# spectrum_2kHz_250Hz.net
KiCad netlist of a schematic drawn in Altium Designer
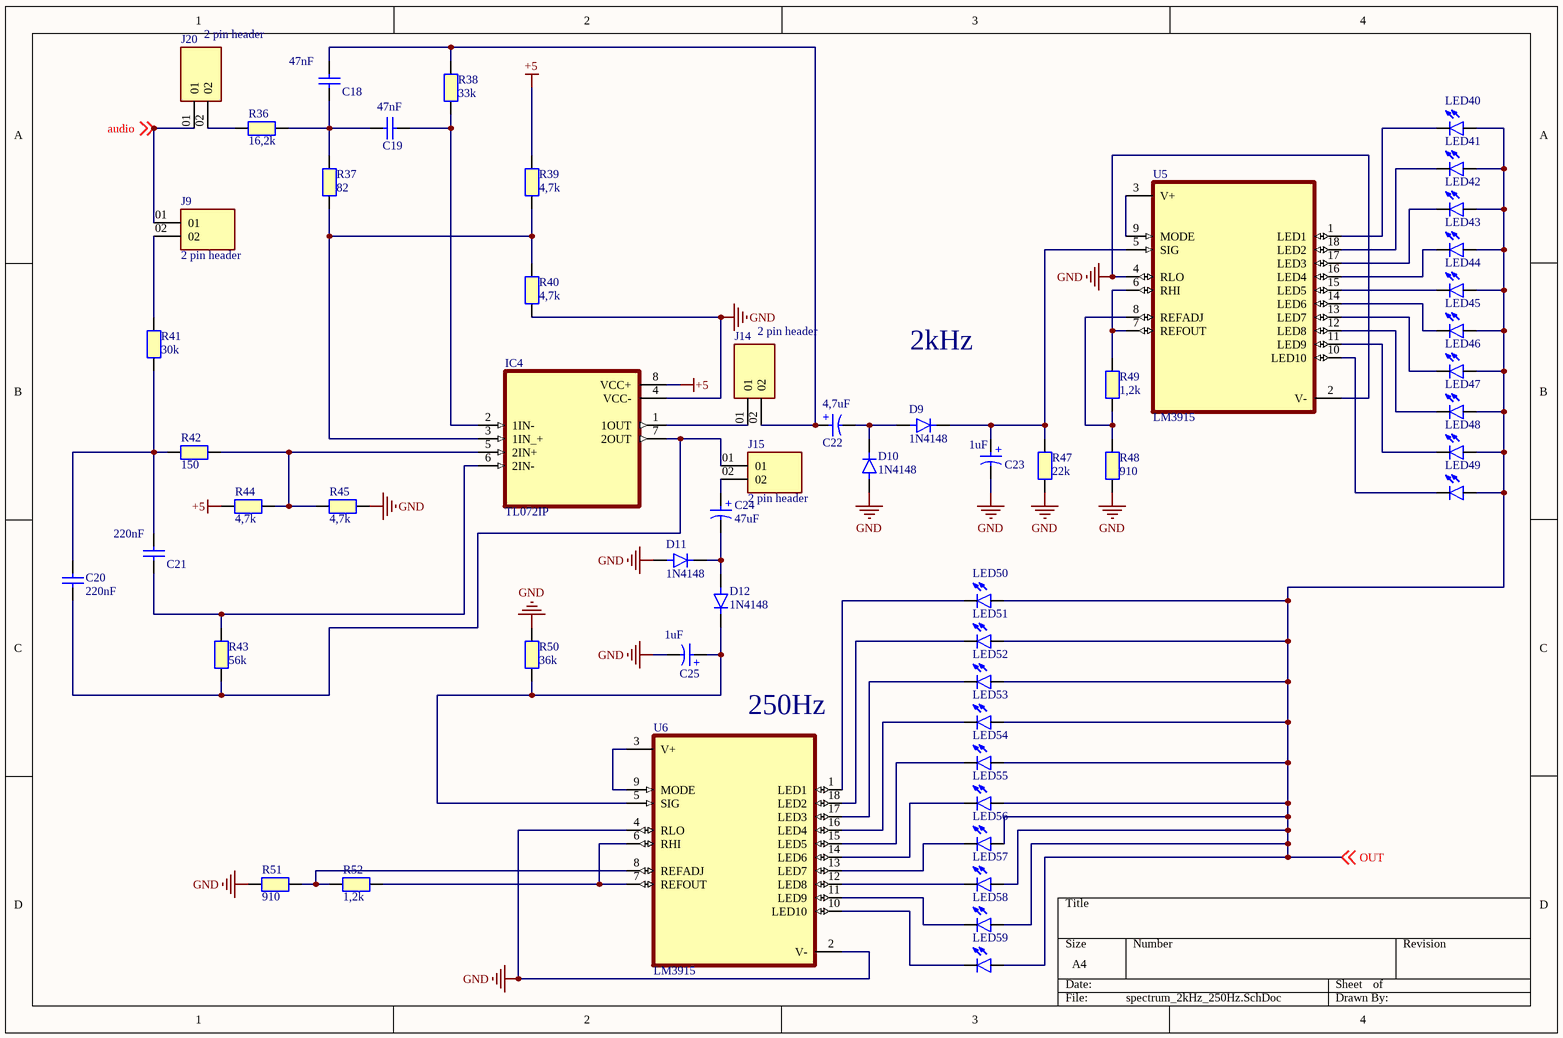
[diagram p0: spectrum_2kHz_250Hz.SchDoc]

(export (version "E")
  (design (tool "Eeschema 10.0.6"))
  (components
    (comp (ref "C18")
      (value "47nF")
      (footprint "CAPC2012X65N")
      (description "47nF ceramic")
      (fields
        (field (name "MANUFACTURER PART NUMBER") "885012004008")
        (field (name "MANUFACTURER") "Wurth Elektronik")
      )
      (libsource (lib "SpectrumComponents") (part "885012004008"))
    )
    (comp (ref "C19")
      (value "47nF")
      (footprint "CAPC2012X65N")
      (description "47nF ceramic")
      (fields
        (field (name "MANUFACTURER PART NUMBER") "885012004008")
        (field (name "MANUFACTURER") "Wurth Elektronik")
      )
      (libsource (lib "SpectrumComponents") (part "885012004008"))
    )
    (comp (ref "C20")
      (value "220nF")
      (footprint "CAPC2012X65N")
      (description "220nF ceramic")
      (fields
        (field (name "MANUFACTURER PART NUMBER") "885012004008")
        (field (name "MANUFACTURER") "Wurth Elektronik")
      )
      (libsource (lib "SpectrumComponents") (part "885012004008"))
    )
    (comp (ref "C21")
      (value "220nF")
      (footprint "CAPC2012X65N")
      (description "220nF ceramic")
      (fields
        (field (name "MANUFACTURER PART NUMBER") "885012004008")
        (field (name "MANUFACTURER") "Wurth Elektronik")
      )
      (libsource (lib "SpectrumComponents") (part "885012004008"))
    )
    (comp (ref "C22")
      (value "4,7uF")
      (footprint "WCAP-ATG8_D5H11")
      (description "Elco 4,7uF")
      (fields
        (field (name "MANUFACTURER PART NUMBER") "860010272005")
        (field (name "MANUFACTURER") "Wurth Elektronik")
      )
      (libsource (lib "SpectrumComponents") (part "860010272005"))
    )
    (comp (ref "C23")
      (value "1uF")
      (footprint "WCAP-ATG8_D5H11")
      (description "WCAP-ATG8 Aluminum Electrolytic Capacitor, Radial, THT, D5 x H11mm, 1uF, 10V")
      (fields
        (field (name "MANUFACTURER PART NUMBER") "860010272005")
        (field (name "MANUFACTURER") "Wurth Elektronik")
      )
      (libsource (lib "SpectrumComponents") (part "860010272005"))
    )
    (comp (ref "C24")
      (value "47uF")
      (footprint "WCAP-ATG8_D5H11")
      (description "Elco 47uF")
      (fields
        (field (name "MANUFACTURER PART NUMBER") "860010272005")
        (field (name "MANUFACTURER") "Wurth Elektronik")
      )
      (libsource (lib "SpectrumComponents") (part "860010272005"))
    )
    (comp (ref "C25")
      (value "1uF")
      (footprint "WCAP-ATG8_D5H11")
      (description "WCAP-ATG8 Aluminum Electrolytic Capacitor, Radial, THT, D5 x H11mm, 1µF, 10V")
      (fields
        (field (name "MANUFACTURER PART NUMBER") "860010272005")
        (field (name "MANUFACTURER") "Wurth Elektronik")
      )
      (libsource (lib "SpectrumComponents") (part "860010272005"))
    )
    (comp (ref "D9")
      (value "1N4148")
      (footprint "DIOAD829W49L456D191")
      (description "Diode Standard 75V 200mA Surface Mount SOD-523F")
      (fields (field (name "MF") "ON Semiconductor"))
      (libsource (lib "SpectrumComponents") (part "1N4148"))
    )
    (comp (ref "D10")
      (value "1N4148")
      (footprint "DIOAD829W49L456D191")
      (description "Diode Standard 75V 200mA Surface Mount SOD-523F")
      (fields (field (name "MF") "ON Semiconductor"))
      (libsource (lib "SpectrumComponents") (part "1N4148"))
    )
    (comp (ref "D11")
      (value "1N4148")
      (footprint "DIOAD829W49L456D191")
      (description "Diode Standard 75V 200mA Surface Mount SOD-523F")
      (fields (field (name "MF") "ON Semiconductor"))
      (libsource (lib "SpectrumComponents") (part "1N4148"))
    )
    (comp (ref "D12")
      (value "1N4148")
      (footprint "DIOAD829W49L456D191")
      (description "Diode Standard 75V 200mA Surface Mount SOD-523F")
      (fields (field (name "MF") "ON Semiconductor"))
      (libsource (lib "SpectrumComponents") (part "1N4148"))
    )
    (comp (ref "IC4")
      (value "TL072IP")
      (footprint "DIP794W45P254L959H508Q8")
      (description "Dual, 30-V, 3-MHz, high slew rate (13-V/Âµs), In to V+, JFET-input op amp")
      (fields (field (name "MF") "Texas Instruments"))
      (libsource (lib "SpectrumComponents") (part "TL072IP"))
    )
    (comp (ref "J9")
      (value "2 pin header")
      (footprint "SpectrumComponents:SAMTEC_HTSW-102-07-TM-S")
      (description "2 pin header Jumper")
      (fields (field (name "MP") "HTSW10207TMS") (field (name "MF") "Samtec"))
      (libsource (lib "") (part "2 pin header_1"))
    )
    (comp (ref "J14")
      (value "2 pin header")
      (footprint "SpectrumComponents:SAMTEC_HTSW-102-07-TM-S")
      (description "2 pin header Jumper")
      (fields (field (name "MP") "HTSW10207TMS") (field (name "MF") "Samtec"))
      (libsource (lib "SpectrumComponents") (part "2 pin header"))
    )
    (comp (ref "J15")
      (value "2 pin header")
      (footprint "SpectrumComponents:SAMTEC_HTSW-102-07-TM-S")
      (description "2 pin header Jumper")
      (fields (field (name "MP") "HTSW10207TMS") (field (name "MF") "Samtec"))
      (libsource (lib "") (part "2 pin header_1"))
    )
    (comp (ref "J20")
      (value "2 pin header")
      (footprint "SpectrumComponents:SAMTEC_HTSW-102-07-TM-S")
      (description "2 pin header Jumper")
      (fields (field (name "MP") "HTSW10207TMS") (field (name "MF") "Samtec"))
      (libsource (lib "SpectrumComponents") (part "2 pin header"))
    )
    (comp (ref "LED40")
      (value "LED 2x3x4")
      (footprint "LED 2x3x4mm")
      (description "Green 569nm LED Indication - Discrete 1.9V Radial")
      (fields (field (name "MP") "TLLG4400") (field (name "MF") "Vishay Semiconductors"))
      (libsource (lib "SpectrumComponents") (part "LED 2x3x4"))
    )
    (comp (ref "LED41")
      (value "LED 2x3x4")
      (footprint "LED 2x3x4mm")
      (description "Green 569nm LED Indication - Discrete 1.9V Radial")
      (fields (field (name "MP") "TLLG4400") (field (name "MF") "Vishay Semiconductors"))
      (libsource (lib "SpectrumComponents") (part "LED 2x3x4"))
    )
    (comp (ref "LED42")
      (value "LED 2x3x4")
      (footprint "LED 2x3x4mm")
      (description "Green 569nm LED Indication - Discrete 1.9V Radial")
      (fields (field (name "MP") "TLLG4400") (field (name "MF") "Vishay Semiconductors"))
      (libsource (lib "SpectrumComponents") (part "LED 2x3x4"))
    )
    (comp (ref "LED43")
      (value "LED 2x3x4")
      (footprint "LED 2x3x4mm")
      (description "Green 569nm LED Indication - Discrete 1.9V Radial")
      (fields (field (name "MP") "TLLG4400") (field (name "MF") "Vishay Semiconductors"))
      (libsource (lib "SpectrumComponents") (part "LED 2x3x4"))
    )
    (comp (ref "LED44")
      (value "LED 2x3x4")
      (footprint "LED 2x3x4mm")
      (description "Green 569nm LED Indication - Discrete 1.9V Radial")
      (fields (field (name "MP") "TLLG4400") (field (name "MF") "Vishay Semiconductors"))
      (libsource (lib "SpectrumComponents") (part "LED 2x3x4"))
    )
    (comp (ref "LED45")
      (value "LED 2x3x4")
      (footprint "LED 2x3x4mm")
      (description "Green 569nm LED Indication - Discrete 1.9V Radial")
      (fields (field (name "MP") "TLLG4400") (field (name "MF") "Vishay Semiconductors"))
      (libsource (lib "SpectrumComponents") (part "LED 2x3x4"))
    )
    (comp (ref "LED46")
      (value "LED 2x3x4")
      (footprint "LED 2x3x4mm")
      (description "Green 569nm LED Indication - Discrete 1.9V Radial")
      (fields (field (name "MP") "TLLG4400") (field (name "MF") "Vishay Semiconductors"))
      (libsource (lib "SpectrumComponents") (part "LED 2x3x4"))
    )
    (comp (ref "LED47")
      (value "LED 2x3x4")
      (footprint "LED 2x3x4mm")
      (description "Green 569nm LED Indication - Discrete 1.9V Radial")
      (fields (field (name "MP") "TLLG4400") (field (name "MF") "Vishay Semiconductors"))
      (libsource (lib "SpectrumComponents") (part "LED 2x3x4"))
    )
    (comp (ref "LED48")
      (value "LED 2x3x4")
      (footprint "LED 2x3x4mm")
      (description "Green 569nm LED Indication - Discrete 1.9V Radial")
      (fields (field (name "MP") "TLLG4400") (field (name "MF") "Vishay Semiconductors"))
      (libsource (lib "SpectrumComponents") (part "LED 2x3x4"))
    )
    (comp (ref "LED49")
      (value "LED 2x3x4")
      (footprint "LED 2x3x4mm")
      (description "Green 569nm LED Indication - Discrete 1.9V Radial")
      (fields (field (name "MP") "TLLG4400") (field (name "MF") "Vishay Semiconductors"))
      (libsource (lib "SpectrumComponents") (part "LED 2x3x4"))
    )
    (comp (ref "LED50")
      (value "LED 2x3x4")
      (footprint "LED 2x3x4mm")
      (description "Green 569nm LED Indication - Discrete 1.9V Radial")
      (fields (field (name "MP") "TLLG4400") (field (name "MF") "Vishay Semiconductors"))
      (libsource (lib "SpectrumComponents") (part "LED 2x3x4"))
    )
    (comp (ref "LED51")
      (value "LED 2x3x4")
      (footprint "LED 2x3x4mm")
      (description "Green 569nm LED Indication - Discrete 1.9V Radial")
      (fields (field (name "MP") "TLLG4400") (field (name "MF") "Vishay Semiconductors"))
      (libsource (lib "SpectrumComponents") (part "LED 2x3x4"))
    )
    (comp (ref "LED52")
      (value "LED 2x3x4")
      (footprint "LED 2x3x4mm")
      (description "Green 569nm LED Indication - Discrete 1.9V Radial")
      (fields (field (name "MP") "TLLG4400") (field (name "MF") "Vishay Semiconductors"))
      (libsource (lib "SpectrumComponents") (part "LED 2x3x4"))
    )
    (comp (ref "LED53")
      (value "LED 2x3x4")
      (footprint "LED 2x3x4mm")
      (description "Green 569nm LED Indication - Discrete 1.9V Radial")
      (fields (field (name "MP") "TLLG4400") (field (name "MF") "Vishay Semiconductors"))
      (libsource (lib "SpectrumComponents") (part "LED 2x3x4"))
    )
    (comp (ref "LED54")
      (value "LED 2x3x4")
      (footprint "LED 2x3x4mm")
      (description "Green 569nm LED Indication - Discrete 1.9V Radial")
      (fields (field (name "MP") "TLLG4400") (field (name "MF") "Vishay Semiconductors"))
      (libsource (lib "SpectrumComponents") (part "LED 2x3x4"))
    )
    (comp (ref "LED55")
      (value "LED 2x3x4")
      (footprint "LED 2x3x4mm")
      (description "Green 569nm LED Indication - Discrete 1.9V Radial")
      (fields (field (name "MP") "TLLG4400") (field (name "MF") "Vishay Semiconductors"))
      (libsource (lib "SpectrumComponents") (part "LED 2x3x4"))
    )
    (comp (ref "LED56")
      (value "LED 2x3x4")
      (footprint "LED 2x3x4mm")
      (description "Green 569nm LED Indication - Discrete 1.9V Radial")
      (fields (field (name "MP") "TLLG4400") (field (name "MF") "Vishay Semiconductors"))
      (libsource (lib "SpectrumComponents") (part "LED 2x3x4"))
    )
    (comp (ref "LED57")
      (value "LED 2x3x4")
      (footprint "LED 2x3x4mm")
      (description "Green 569nm LED Indication - Discrete 1.9V Radial")
      (fields (field (name "MP") "TLLG4400") (field (name "MF") "Vishay Semiconductors"))
      (libsource (lib "SpectrumComponents") (part "LED 2x3x4"))
    )
    (comp (ref "LED58")
      (value "LED 2x3x4")
      (footprint "LED 2x3x4mm")
      (description "Green 569nm LED Indication - Discrete 1.9V Radial")
      (fields (field (name "MP") "TLLG4400") (field (name "MF") "Vishay Semiconductors"))
      (libsource (lib "SpectrumComponents") (part "LED 2x3x4"))
    )
    (comp (ref "LED59")
      (value "LED 2x3x4")
      (footprint "LED 2x3x4mm")
      (description "Green 569nm LED Indication - Discrete 1.9V Radial")
      (fields (field (name "MP") "TLLG4400") (field (name "MF") "Vishay Semiconductors"))
      (libsource (lib "SpectrumComponents") (part "LED 2x3x4"))
    )
    (comp (ref "R36")
      (value "16,2k")
      (footprint "RESC2012X50N")
      (description "16.2k Resistor 0805")
      (fields (field (name "PART NUMBER") "TNPW080510K0BETA") (field (name "MANUFACTURER") "Vishay Dale"))
      (libsource (lib "") (part "RESISTOR 0805_3"))
    )
    (comp (ref "R37")
      (value "82")
      (footprint "RESC2012X50N")
      (description "82Ohm Resistor 0805")
      (fields (field (name "PART NUMBER") "TNPW080510K0BETA") (field (name "MANUFACTURER") "Vishay Dale"))
      (libsource (lib "SpectrumComponents") (part "RESISTOR 0805"))
    )
    (comp (ref "R38")
      (value "33k")
      (footprint "RESC2012X50N")
      (description "33k Resistor 0805")
      (fields (field (name "PART NUMBER") "TNPW080510K0BETA") (field (name "MANUFACTURER") "Vishay Dale"))
      (libsource (lib "SpectrumComponents") (part "RESISTOR 0805"))
    )
    (comp (ref "R39")
      (value "4,7k")
      (footprint "RESC2012X50N")
      (description "4,7k Resistor 0805")
      (fields (field (name "PART NUMBER") "TNPW080510K0BETA") (field (name "MANUFACTURER") "Vishay Dale"))
      (libsource (lib "SpectrumComponents") (part "RESISTOR 0805"))
    )
    (comp (ref "R40")
      (value "4,7k")
      (footprint "RESC2012X50N")
      (description "4,7k Resistor 0805")
      (fields (field (name "PART NUMBER") "TNPW080510K0BETA") (field (name "MANUFACTURER") "Vishay Dale"))
      (libsource (lib "SpectrumComponents") (part "RESISTOR 0805"))
    )
    (comp (ref "R41")
      (value "30k")
      (footprint "RESC2012X50N")
      (description "30k Resistor 0805")
      (fields (field (name "PART NUMBER") "TNPW080510K0BETA") (field (name "MANUFACTURER") "Vishay Dale"))
      (libsource (lib "SpectrumComponents") (part "RESISTOR 0805"))
    )
    (comp (ref "R42")
      (value "150")
      (footprint "RESC2012X50N")
      (description "150 Resistor 0805")
      (fields (field (name "PART NUMBER") "TNPW080510K0BETA") (field (name "MANUFACTURER") "Vishay Dale"))
      (libsource (lib "") (part "RESISTOR 0805_1"))
    )
    (comp (ref "R43")
      (value "56k")
      (footprint "RESC2012X50N")
      (description "56k Resistor 0805")
      (fields (field (name "PART NUMBER") "TNPW080510K0BETA") (field (name "MANUFACTURER") "Vishay Dale"))
      (libsource (lib "SpectrumComponents") (part "RESISTOR 0805"))
    )
    (comp (ref "R44")
      (value "4,7k")
      (footprint "RESC2012X50N")
      (description "4,7k Resistor 0805")
      (fields (field (name "PART NUMBER") "TNPW080510K0BETA") (field (name "MANUFACTURER") "Vishay Dale"))
      (libsource (lib "") (part "RESISTOR 0805_1"))
    )
    (comp (ref "R45")
      (value "4,7k")
      (footprint "RESC2012X50N")
      (description "4,7k Resistor 0805")
      (fields (field (name "PART NUMBER") "TNPW080510K0BETA") (field (name "MANUFACTURER") "Vishay Dale"))
      (libsource (lib "") (part "RESISTOR 0805_3"))
    )
    (comp (ref "R47")
      (value "22k")
      (footprint "RESC2012X50N")
      (description "22k Resistor 0805")
      (fields (field (name "PART NUMBER") "TNPW080510K0BETA") (field (name "MANUFACTURER") "Vishay Dale"))
      (libsource (lib "SpectrumComponents") (part "RESISTOR 0805"))
    )
    (comp (ref "R48")
      (value "910")
      (footprint "RESC2012X50N")
      (description "910 Resistor 0805")
      (fields (field (name "PART NUMBER") "TNPW080510K0BETA") (field (name "MANUFACTURER") "Vishay Dale"))
      (libsource (lib "") (part "RESISTOR 0805_2"))
    )
    (comp (ref "R49")
      (value "1,2k")
      (footprint "RESC2012X50N")
      (description "1,2k Resistor 0805")
      (fields (field (name "PART NUMBER") "TNPW080510K0BETA") (field (name "MANUFACTURER") "Vishay Dale"))
      (libsource (lib "") (part "RESISTOR 0805_2"))
    )
    (comp (ref "R50")
      (value "36k")
      (footprint "RESC2012X50N")
      (description "4,7k Resistor 0805")
      (fields (field (name "PART NUMBER") "TNPW080510K0BETA") (field (name "MANUFACTURER") "Vishay Dale"))
      (libsource (lib "") (part "RESISTOR 0805_2"))
    )
    (comp (ref "R51")
      (value "910")
      (footprint "RESC2012X50N")
      (description "910 Resistor 0805")
      (fields (field (name "PART NUMBER") "TNPW080510K0BETA") (field (name "MANUFACTURER") "Vishay Dale"))
      (libsource (lib "") (part "RESISTOR 0805_1"))
    )
    (comp (ref "R52")
      (value "1,2k")
      (footprint "RESC2012X50N")
      (description "1,2k Resistor 0805")
      (fields (field (name "PART NUMBER") "TNPW080510K0BETA") (field (name "MANUFACTURER") "Vishay Dale"))
      (libsource (lib "") (part "RESISTOR 0805_1"))
    )
    (comp (ref "U5")
      (value "LM3915")
      (footprint "SpectrumComponents:DIP952W45P254L2336H533Q18")
      (fields (field (name "MP") "LM3914N-1"))
      (libsource (lib "SpectrumComponents") (part "LM3915"))
    )
    (comp (ref "U6")
      (value "LM3915")
      (footprint "SpectrumComponents:DIP952W45P254L2336H533Q18")
      (fields (field (name "MP") "LM3914N-1"))
      (libsource (lib "SpectrumComponents") (part "LM3915"))
    )
  )
  (nets
    (net (code "1") (name "+5") (class "Default")
      (node (ref "IC4") (pin "8") (pinfunction "VCC+_8") (pintype "power_in"))
      (node (ref "R39") (pin "2") (pinfunction "2_2") (pintype "passive"))
      (node (ref "R44") (pin "2") (pinfunction "2_2") (pintype "passive"))
    )
    (net (code "2") (name "GND") (class "Default")
      (node (ref "C23") (pin "2") (pinfunction "N_2") (pintype "passive"))
      (node (ref "C25") (pin "2") (pinfunction "N_2") (pintype "passive"))
      (node (ref "D10") (pin "A") (pinfunction "A_A") (pintype "passive"))
      (node (ref "D11") (pin "A") (pinfunction "A_A") (pintype "passive"))
      (node (ref "IC4") (pin "4") (pinfunction "VCC-_4") (pintype "power_in"))
      (node (ref "R40") (pin "1") (pinfunction "1_1") (pintype "passive"))
      (node (ref "R45") (pin "2") (pinfunction "2_2") (pintype "passive"))
      (node (ref "R47") (pin "1") (pinfunction "1_1") (pintype "passive"))
      (node (ref "R48") (pin "2") (pinfunction "2_2") (pintype "passive"))
      (node (ref "R50") (pin "1") (pinfunction "1_1") (pintype "passive"))
      (node (ref "R51") (pin "2") (pinfunction "2_2") (pintype "passive"))
      (node (ref "U5") (pin "2") (pinfunction "V-_2") (pintype "power_in"))
      (node (ref "U5") (pin "4") (pinfunction "RLO_4") (pintype "bidirectional"))
      (node (ref "U6") (pin "2") (pinfunction "V-_2") (pintype "power_in"))
      (node (ref "U6") (pin "4") (pinfunction "RLO_4") (pintype "bidirectional"))
    )
    (net (code "3") (name "Net-(C18-Pad1)") (class "Default")
      (node (ref "C18") (pin "1") (pinfunction "1_1") (pintype "passive"))
      (node (ref "C19") (pin "1") (pinfunction "1_1") (pintype "passive"))
      (node (ref "R36") (pin "2") (pinfunction "2_2") (pintype "passive"))
      (node (ref "R37") (pin "2") (pinfunction "2_2") (pintype "passive"))
    )
    (net (code "4") (name "Net-(C20-Pad2)") (class "Default")
      (node (ref "C20") (pin "2") (pinfunction "2_2") (pintype "passive"))
      (node (ref "C21") (pin "2") (pinfunction "2_2") (pintype "passive"))
      (node (ref "R41") (pin "1") (pinfunction "1_1") (pintype "passive"))
      (node (ref "R42") (pin "2") (pinfunction "2_2") (pintype "passive"))
    )
    (net (code "5") (name "Net-(C22-N)") (class "Default")
      (node (ref "C22") (pin "2") (pinfunction "N_2") (pintype "passive"))
      (node (ref "D10") (pin "C") (pinfunction "C_C") (pintype "passive"))
      (node (ref "D9") (pin "A") (pinfunction "A_A") (pintype "passive"))
    )
    (net (code "6") (name "Net-(C22-P)") (class "Default")
      (node (ref "C18") (pin "2") (pinfunction "2_2") (pintype "passive"))
      (node (ref "C22") (pin "1") (pinfunction "P_1") (pintype "passive"))
      (node (ref "J14") (pin "02") (pinfunction "02_02") (pintype "passive"))
      (node (ref "R38") (pin "2") (pinfunction "2_2") (pintype "passive"))
    )
    (net (code "7") (name "Net-(C23-P)") (class "Default")
      (node (ref "C23") (pin "1") (pinfunction "P_1") (pintype "passive"))
      (node (ref "D9") (pin "C") (pinfunction "C_C") (pintype "passive"))
      (node (ref "R47") (pin "2") (pinfunction "2_2") (pintype "passive"))
      (node (ref "U5") (pin "5") (pinfunction "SIG_5") (pintype "input"))
    )
    (net (code "8") (name "Net-(C24-N)") (class "Default")
      (node (ref "C24") (pin "2") (pinfunction "N_2") (pintype "passive"))
      (node (ref "D11") (pin "C") (pinfunction "C_C") (pintype "passive"))
      (node (ref "D12") (pin "A") (pinfunction "A_A") (pintype "passive"))
    )
    (net (code "9") (name "Net-(C24-P)") (class "Default")
      (node (ref "C24") (pin "1") (pinfunction "P_1") (pintype "passive"))
      (node (ref "J15") (pin "02") (pinfunction "02_02") (pintype "passive"))
    )
    (net (code "10") (name "Net-(C25-P)") (class "Default")
      (node (ref "C25") (pin "1") (pinfunction "P_1") (pintype "passive"))
      (node (ref "D12") (pin "C") (pinfunction "C_C") (pintype "passive"))
      (node (ref "R50") (pin "2") (pinfunction "2_2") (pintype "passive"))
      (node (ref "U6") (pin "5") (pinfunction "SIG_5") (pintype "input"))
    )
    (net (code "11") (name "Net-(IC4-1IN-)") (class "Default")
      (node (ref "C19") (pin "2") (pinfunction "2_2") (pintype "passive"))
      (node (ref "IC4") (pin "2") (pinfunction "1IN-_2") (pintype "input"))
      (node (ref "R38") (pin "1") (pinfunction "1_1") (pintype "passive"))
    )
    (net (code "12") (name "Net-(IC4-1IN_+)") (class "Default")
      (node (ref "IC4") (pin "3") (pinfunction "1IN_+_3") (pintype "input"))
      (node (ref "R37") (pin "1") (pinfunction "1_1") (pintype "passive"))
      (node (ref "R39") (pin "1") (pinfunction "1_1") (pintype "passive"))
      (node (ref "R40") (pin "2") (pinfunction "2_2") (pintype "passive"))
    )
    (net (code "13") (name "Net-(IC4-1OUT)") (class "Default")
      (node (ref "IC4") (pin "1") (pinfunction "1OUT_1") (pintype "output"))
      (node (ref "J14") (pin "01") (pinfunction "01_01") (pintype "passive"))
    )
    (net (code "14") (name "Net-(IC4-2IN+)") (class "Default")
      (node (ref "IC4") (pin "5") (pinfunction "2IN+_5") (pintype "input"))
      (node (ref "R42") (pin "1") (pinfunction "1_1") (pintype "passive"))
      (node (ref "R44") (pin "1") (pinfunction "1_1") (pintype "passive"))
      (node (ref "R45") (pin "1") (pinfunction "1_1") (pintype "passive"))
    )
    (net (code "15") (name "Net-(IC4-2IN-)") (class "Default")
      (node (ref "C21") (pin "1") (pinfunction "1_1") (pintype "passive"))
      (node (ref "IC4") (pin "6") (pinfunction "2IN-_6") (pintype "input"))
      (node (ref "R43") (pin "2") (pinfunction "2_2") (pintype "passive"))
    )
    (net (code "16") (name "Net-(IC4-2OUT)") (class "Default")
      (node (ref "C20") (pin "1") (pinfunction "1_1") (pintype "passive"))
      (node (ref "IC4") (pin "7") (pinfunction "2OUT_7") (pintype "output"))
      (node (ref "J15") (pin "01") (pinfunction "01_01") (pintype "passive"))
      (node (ref "R43") (pin "1") (pinfunction "1_1") (pintype "passive"))
    )
    (net (code "17") (name "Net-(J9-Pad02)") (class "Default")
      (node (ref "J9") (pin "02") (pinfunction "02_02") (pintype "passive"))
      (node (ref "R41") (pin "2") (pinfunction "2_2") (pintype "passive"))
    )
    (net (code "18") (name "Net-(J20-Pad02)") (class "Default")
      (node (ref "J20") (pin "02") (pinfunction "02_02") (pintype "passive"))
      (node (ref "R36") (pin "1") (pinfunction "1_1") (pintype "passive"))
    )
    (net (code "19") (name "Net-(LED40-C)") (class "Default")
      (node (ref "LED40") (pin "K") (pinfunction "C_K") (pintype "passive"))
      (node (ref "U5") (pin "1") (pinfunction "LED1_1") (pintype "bidirectional"))
    )
    (net (code "20") (name "Net-(LED41-C)") (class "Default")
      (node (ref "LED41") (pin "K") (pinfunction "C_K") (pintype "passive"))
      (node (ref "U5") (pin "18") (pinfunction "LED2_18") (pintype "bidirectional"))
    )
    (net (code "21") (name "Net-(LED42-C)") (class "Default")
      (node (ref "LED42") (pin "K") (pinfunction "C_K") (pintype "passive"))
      (node (ref "U5") (pin "17") (pinfunction "LED3_17") (pintype "bidirectional"))
    )
    (net (code "22") (name "Net-(LED43-C)") (class "Default")
      (node (ref "LED43") (pin "K") (pinfunction "C_K") (pintype "passive"))
      (node (ref "U5") (pin "16") (pinfunction "LED4_16") (pintype "bidirectional"))
    )
    (net (code "23") (name "Net-(LED44-C)") (class "Default")
      (node (ref "LED44") (pin "K") (pinfunction "C_K") (pintype "passive"))
      (node (ref "U5") (pin "15") (pinfunction "LED5_15") (pintype "bidirectional"))
    )
    (net (code "24") (name "Net-(LED45-C)") (class "Default")
      (node (ref "LED45") (pin "K") (pinfunction "C_K") (pintype "passive"))
      (node (ref "U5") (pin "14") (pinfunction "LED6_14") (pintype "bidirectional"))
    )
    (net (code "25") (name "Net-(LED46-C)") (class "Default")
      (node (ref "LED46") (pin "K") (pinfunction "C_K") (pintype "passive"))
      (node (ref "U5") (pin "13") (pinfunction "LED7_13") (pintype "bidirectional"))
    )
    (net (code "26") (name "Net-(LED47-C)") (class "Default")
      (node (ref "LED47") (pin "K") (pinfunction "C_K") (pintype "passive"))
      (node (ref "U5") (pin "12") (pinfunction "LED8_12") (pintype "bidirectional"))
    )
    (net (code "27") (name "Net-(LED48-C)") (class "Default")
      (node (ref "LED48") (pin "K") (pinfunction "C_K") (pintype "passive"))
      (node (ref "U5") (pin "11") (pinfunction "LED9_11") (pintype "bidirectional"))
    )
    (net (code "28") (name "Net-(LED49-C)") (class "Default")
      (node (ref "LED49") (pin "K") (pinfunction "C_K") (pintype "passive"))
      (node (ref "U5") (pin "10") (pinfunction "LED10_10") (pintype "bidirectional"))
    )
    (net (code "29") (name "Net-(LED50-C)") (class "Default")
      (node (ref "LED50") (pin "K") (pinfunction "C_K") (pintype "passive"))
      (node (ref "U6") (pin "1") (pinfunction "LED1_1") (pintype "bidirectional"))
    )
    (net (code "30") (name "Net-(LED51-C)") (class "Default")
      (node (ref "LED51") (pin "K") (pinfunction "C_K") (pintype "passive"))
      (node (ref "U6") (pin "18") (pinfunction "LED2_18") (pintype "bidirectional"))
    )
    (net (code "31") (name "Net-(LED52-C)") (class "Default")
      (node (ref "LED52") (pin "K") (pinfunction "C_K") (pintype "passive"))
      (node (ref "U6") (pin "17") (pinfunction "LED3_17") (pintype "bidirectional"))
    )
    (net (code "32") (name "Net-(LED53-C)") (class "Default")
      (node (ref "LED53") (pin "K") (pinfunction "C_K") (pintype "passive"))
      (node (ref "U6") (pin "16") (pinfunction "LED4_16") (pintype "bidirectional"))
    )
    (net (code "33") (name "Net-(LED54-C)") (class "Default")
      (node (ref "LED54") (pin "K") (pinfunction "C_K") (pintype "passive"))
      (node (ref "U6") (pin "15") (pinfunction "LED5_15") (pintype "bidirectional"))
    )
    (net (code "34") (name "Net-(LED55-C)") (class "Default")
      (node (ref "LED55") (pin "K") (pinfunction "C_K") (pintype "passive"))
      (node (ref "U6") (pin "14") (pinfunction "LED6_14") (pintype "bidirectional"))
    )
    (net (code "35") (name "Net-(LED56-C)") (class "Default")
      (node (ref "LED56") (pin "K") (pinfunction "C_K") (pintype "passive"))
      (node (ref "U6") (pin "13") (pinfunction "LED7_13") (pintype "bidirectional"))
    )
    (net (code "36") (name "Net-(LED57-C)") (class "Default")
      (node (ref "LED57") (pin "K") (pinfunction "C_K") (pintype "passive"))
      (node (ref "U6") (pin "12") (pinfunction "LED8_12") (pintype "bidirectional"))
    )
    (net (code "37") (name "Net-(LED58-C)") (class "Default")
      (node (ref "LED58") (pin "K") (pinfunction "C_K") (pintype "passive"))
      (node (ref "U6") (pin "11") (pinfunction "LED9_11") (pintype "bidirectional"))
    )
    (net (code "38") (name "Net-(LED59-C)") (class "Default")
      (node (ref "LED59") (pin "K") (pinfunction "C_K") (pintype "passive"))
      (node (ref "U6") (pin "10") (pinfunction "LED10_10") (pintype "bidirectional"))
    )
    (net (code "39") (name "Net-(U5-MODE)") (class "Default")
      (node (ref "U5") (pin "3") (pinfunction "V+_3") (pintype "power_in"))
      (node (ref "U5") (pin "9") (pinfunction "MODE_9") (pintype "input"))
    )
    (net (code "40") (name "Net-(U5-REFADJ)") (class "Default")
      (node (ref "R48") (pin "1") (pinfunction "1_1") (pintype "passive"))
      (node (ref "R49") (pin "2") (pinfunction "2_2") (pintype "passive"))
      (node (ref "U5") (pin "8") (pinfunction "REFADJ_8") (pintype "bidirectional"))
    )
    (net (code "41") (name "Net-(U5-REFOUT)") (class "Default")
      (node (ref "R49") (pin "1") (pinfunction "1_1") (pintype "passive"))
      (node (ref "U5") (pin "6") (pinfunction "RHI_6") (pintype "bidirectional"))
      (node (ref "U5") (pin "7") (pinfunction "REFOUT_7") (pintype "bidirectional"))
    )
    (net (code "42") (name "Net-(U6-MODE)") (class "Default")
      (node (ref "U6") (pin "3") (pinfunction "V+_3") (pintype "power_in"))
      (node (ref "U6") (pin "9") (pinfunction "MODE_9") (pintype "input"))
    )
    (net (code "43") (name "Net-(U6-REFADJ)") (class "Default")
      (node (ref "R51") (pin "1") (pinfunction "1_1") (pintype "passive"))
      (node (ref "R52") (pin "2") (pinfunction "2_2") (pintype "passive"))
      (node (ref "U6") (pin "8") (pinfunction "REFADJ_8") (pintype "bidirectional"))
    )
    (net (code "44") (name "Net-(U6-REFOUT)") (class "Default")
      (node (ref "R52") (pin "1") (pinfunction "1_1") (pintype "passive"))
      (node (ref "U6") (pin "6") (pinfunction "RHI_6") (pintype "bidirectional"))
      (node (ref "U6") (pin "7") (pinfunction "REFOUT_7") (pintype "bidirectional"))
    )
    (net (code "45") (name "OUT") (class "Default")
      (node (ref "LED40") (pin "A") (pinfunction "A_A") (pintype "passive"))
      (node (ref "LED41") (pin "A") (pinfunction "A_A") (pintype "passive"))
      (node (ref "LED42") (pin "A") (pinfunction "A_A") (pintype "passive"))
      (node (ref "LED43") (pin "A") (pinfunction "A_A") (pintype "passive"))
      (node (ref "LED44") (pin "A") (pinfunction "A_A") (pintype "passive"))
      (node (ref "LED45") (pin "A") (pinfunction "A_A") (pintype "passive"))
      (node (ref "LED46") (pin "A") (pinfunction "A_A") (pintype "passive"))
      (node (ref "LED47") (pin "A") (pinfunction "A_A") (pintype "passive"))
      (node (ref "LED48") (pin "A") (pinfunction "A_A") (pintype "passive"))
      (node (ref "LED49") (pin "A") (pinfunction "A_A") (pintype "passive"))
      (node (ref "LED50") (pin "A") (pinfunction "A_A") (pintype "passive"))
      (node (ref "LED51") (pin "A") (pinfunction "A_A") (pintype "passive"))
      (node (ref "LED52") (pin "A") (pinfunction "A_A") (pintype "passive"))
      (node (ref "LED53") (pin "A") (pinfunction "A_A") (pintype "passive"))
      (node (ref "LED54") (pin "A") (pinfunction "A_A") (pintype "passive"))
      (node (ref "LED55") (pin "A") (pinfunction "A_A") (pintype "passive"))
      (node (ref "LED56") (pin "A") (pinfunction "A_A") (pintype "passive"))
      (node (ref "LED57") (pin "A") (pinfunction "A_A") (pintype "passive"))
      (node (ref "LED58") (pin "A") (pinfunction "A_A") (pintype "passive"))
      (node (ref "LED59") (pin "A") (pinfunction "A_A") (pintype "passive"))
    )
    (net (code "46") (name "audio") (class "Default")
      (node (ref "J20") (pin "01") (pinfunction "01_01") (pintype "passive"))
      (node (ref "J9") (pin "01") (pinfunction "01_01") (pintype "passive"))
    )
  )
)
